# SDcard.net
KiCad netlist of a schematic drawn in Altium Designer
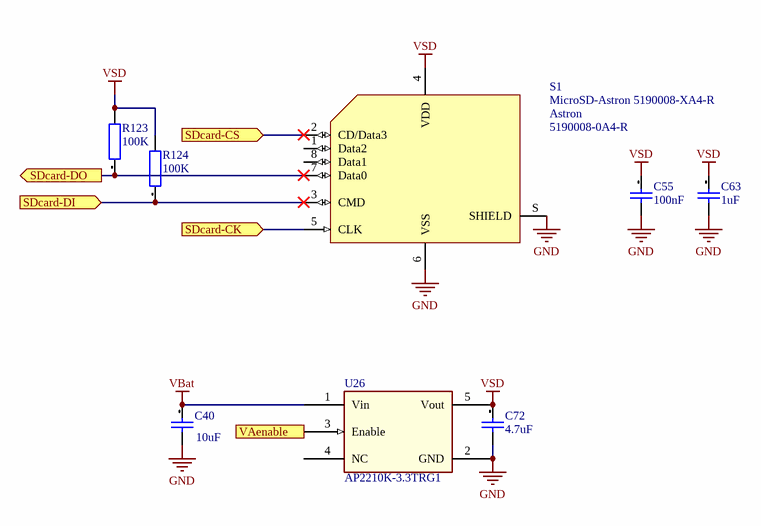
[diagram p0: SDcard.SchDoc]

(export (version "E")
  (design (tool "Eeschema 10.0.6"))
  (components
    (comp (ref "C40")
      (value "10uF")
      (footprint "CAPC1005X05N")
      (description "Capacitor")
      (fields (field (name "MANUFACTURER") "Kemet") (field (name "VOLTAGE") "6.3"))
      (libsource (lib "LSRO1Altium") (part "CAP-NP"))
    )
    (comp (ref "C55")
      (value "100nF")
      (footprint "CAPC1005X05N")
      (description "Capacitor")
      (fields (field (name "MANUFACTURER") "Kemet") (field (name "VOLTAGE") "50"))
      (libsource (lib "LSRO1Altium") (part "CAP-NP"))
    )
    (comp (ref "C63")
      (value "1uF")
      (footprint "CAPC1005X05N")
      (description "Capacitor")
      (fields (field (name "MANUFACTURER") "Murata") (field (name "VOLTAGE") "25"))
      (libsource (lib "LSRO1Altium") (part "CAP-NP"))
    )
    (comp (ref "C72")
      (value "4.7uF")
      (footprint "CAPC1005X05N")
      (description "Capacitor")
      (fields (field (name "MANUFACTURER") "Kemet") (field (name "VOLTAGE") "6.3"))
      (libsource (lib "LSRO1Altium") (part "CAP-NP"))
    )
    (comp (ref "R123")
      (value "100K")
      (footprint "RESC1005X04N")
      (description "Resistor")
      (fields (field (name "TOLERANCE") "+/-1") (field (name "MANUFACTURER") "Vishay"))
      (libsource (lib "LSRO1Altium") (part "RES"))
    )
    (comp (ref "R124")
      (value "100K")
      (footprint "RESC1005X04N")
      (description "Resistor")
      (fields (field (name "TOLERANCE") "+/-1") (field (name "MANUFACTURER") "Vishay"))
      (libsource (lib "LSRO1Altium") (part "RES"))
    )
    (comp (ref "S1")
      (value "MicroSD-Astron 5190008-XA4-R")
      (footprint "CONnectors_Manufacturers:Astron 5190008-XA4-R")
      (description "MicroSD Card connector 5190008-XA4-R")
      (fields (field (name "MANUFACTURER") "Astron") (field (name "MFG PART NUMBER") "5190008-0A4-R"))
      (libsource (lib "Connectors") (part "SD-Card-Micro-ASLTRON 5190008-XA4-R"))
    )
    (comp (ref "U26")
      (value "AP2210K-3.3TRG1")
      (footprint "SOT - SmallOutlineTransistor:SOT95P285X100-5N")
      (description "300mA, Low Quiescent Current, Fast Transient LDO")
      (libsource (lib "ICs") (part "AP7331"))
    )
  )
  (nets
    (net (code "1") (name "/SDcard-CK") (class "Default")
      (node (ref "S1") (pin "5") (pinfunction "CLK_5") (pintype "input"))
    )
    (net (code "2") (name "/SDcard-CS") (class "Default")
      (node (ref "S1") (pin "2") (pinfunction "CD/Data3_2") (pintype "bidirectional+no_connect"))
    )
    (net (code "3") (name "/SDcard-DI") (class "Default")
      (node (ref "R124") (pin "1") (pinfunction "1_1") (pintype "passive"))
      (node (ref "S1") (pin "3") (pinfunction "CMD_3") (pintype "bidirectional"))
    )
    (net (code "4") (name "/SDcard-DO") (class "Default")
      (node (ref "R123") (pin "1") (pinfunction "1_1") (pintype "passive"))
      (node (ref "S1") (pin "7") (pinfunction "Data0_7") (pintype "bidirectional"))
    )
    (net (code "5") (name "/VAenable") (class "Default")
      (node (ref "U26") (pin "3") (pinfunction "Enable_3") (pintype "input"))
    )
    (net (code "6") (name "GND") (class "Default")
      (node (ref "C40") (pin "2") (pinfunction "2_2") (pintype "passive"))
      (node (ref "C55") (pin "2") (pinfunction "2_2") (pintype "passive"))
      (node (ref "C63") (pin "2") (pinfunction "2_2") (pintype "passive"))
      (node (ref "C72") (pin "2") (pinfunction "2_2") (pintype "passive"))
      (node (ref "S1") (pin "6") (pinfunction "VSS_6") (pintype "power_in"))
      (node (ref "S1") (pin "S") (pinfunction "SHIELD_S") (pintype "passive"))
      (node (ref "U26") (pin "2") (pinfunction "GND_2") (pintype "power_in"))
    )
    (net (code "7") (name "VBat") (class "Default")
      (node (ref "C40") (pin "1") (pinfunction "1_1") (pintype "passive"))
      (node (ref "U26") (pin "1") (pinfunction "Vin_1") (pintype "power_in"))
    )
    (net (code "8") (name "VSD") (class "Default")
      (node (ref "C55") (pin "1") (pinfunction "1_1") (pintype "passive"))
      (node (ref "C63") (pin "1") (pinfunction "1_1") (pintype "passive"))
      (node (ref "C72") (pin "1") (pinfunction "1_1") (pintype "passive"))
      (node (ref "R123") (pin "2") (pinfunction "2_2") (pintype "passive"))
      (node (ref "R124") (pin "2") (pinfunction "2_2") (pintype "passive"))
      (node (ref "S1") (pin "4") (pinfunction "VDD_4") (pintype "power_in"))
      (node (ref "U26") (pin "5") (pinfunction "Vout_5") (pintype "power_in"))
    )
    (net (code "9") (name "unconnected-(S1-Data1-Pad8)") (class "Default")
      (node (ref "S1") (pin "8") (pinfunction "Data1_8") (pintype "bidirectional"))
    )
    (net (code "10") (name "unconnected-(S1-Data2-Pad1)") (class "Default")
      (node (ref "S1") (pin "1") (pinfunction "Data2_1") (pintype "bidirectional"))
    )
    (net (code "11") (name "unconnected-(U26-NC-Pad4)") (class "Default")
      (node (ref "U26") (pin "4") (pinfunction "NC_4") (pintype "passive"))
    )
  )
)
